# StuderA80ReproExtend_V0_2_RCA.net
KiCad netlist of a schematic drawn in Altium Designer
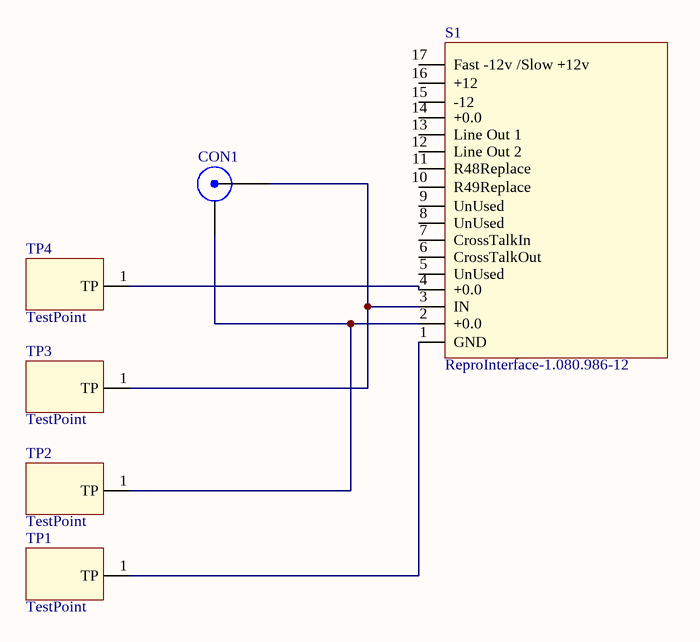
[diagram p0: StuderA80ReproExtend_V0.2_RCA.SchDoc]

(export (version "E")
  (design (tool "Eeschema 10.0.6"))
  (components
    (comp (ref "CON1")
      (value "RCA")
      (footprint "RCA-RJ255")
      (description "RCA Connector")
      (fields (field (name "PUBLISHER") "Altium Limited"))
      (libsource (lib "Connectors") (part "RCA"))
    )
    (comp (ref "S1")
      (value "ReproInterface-1.080.986-12")
      (footprint "ReproInterface")
      (description "Studer A80 RC Reproduce Card 1.080.986-12 Interface")
      (libsource (lib "Studer") (part "ReproInterface-1.080.986-12"))
    )
    (comp (ref "TP1")
      (value "TestPoint")
      (footprint "TP-1.0mm")
      (libsource (lib "Studer") (part "TestPoint"))
    )
    (comp (ref "TP2")
      (value "TestPoint")
      (footprint "TP-1.0mm")
      (libsource (lib "Studer") (part "TestPoint"))
    )
    (comp (ref "TP3")
      (value "TestPoint")
      (footprint "TP-1.0mm")
      (libsource (lib "Studer") (part "TestPoint"))
    )
    (comp (ref "TP4")
      (value "TestPoint")
      (footprint "TP-1.0mm")
      (libsource (lib "Studer") (part "TestPoint"))
    )
  )
  (nets
    (net (code "1") (name "Net-(CON1-X)") (class "Default")
      (node (ref "CON1") (pin "1") (pinfunction "X_1") (pintype "passive"))
      (node (ref "S1") (pin "3") (pinfunction "IN_3") (pintype "passive"))
      (node (ref "TP3") (pin "1") (pinfunction "TP_1") (pintype "passive"))
    )
    (net (code "2") (name "Net-(CON1-Y)") (class "Default")
      (node (ref "CON1") (pin "2") (pinfunction "Y_2") (pintype "passive"))
      (node (ref "S1") (pin "2") (pinfunction "+0.0_2") (pintype "passive"))
      (node (ref "TP2") (pin "1") (pinfunction "TP_1") (pintype "passive"))
    )
    (net (code "3") (name "Net-(S1-GND)") (class "Default")
      (node (ref "S1") (pin "1") (pinfunction "GND_1") (pintype "passive"))
      (node (ref "TP1") (pin "1") (pinfunction "TP_1") (pintype "passive"))
    )
    (net (code "4") (name "Net-(TP4-TP)") (class "Default")
      (node (ref "S1") (pin "4") (pinfunction "+0.0_4") (pintype "passive"))
      (node (ref "TP4") (pin "1") (pinfunction "TP_1") (pintype "passive"))
    )
    (net (code "5") (name "unconnected-(S1-+0.0-Pad14)") (class "Default")
      (node (ref "S1") (pin "14") (pinfunction "+0.0_14") (pintype "passive"))
    )
    (net (code "6") (name "unconnected-(S1-+12-Pad16)") (class "Default")
      (node (ref "S1") (pin "16") (pinfunction "+12_16") (pintype "passive"))
    )
    (net (code "7") (name "unconnected-(S1--12-Pad15)") (class "Default")
      (node (ref "S1") (pin "15") (pinfunction "-12_15") (pintype "passive"))
    )
    (net (code "8") (name "unconnected-(S1-CrossTalkIn-Pad7)") (class "Default")
      (node (ref "S1") (pin "7") (pinfunction "CrossTalkIn_7") (pintype "passive"))
    )
    (net (code "9") (name "unconnected-(S1-CrossTalkOut-Pad6)") (class "Default")
      (node (ref "S1") (pin "6") (pinfunction "CrossTalkOut_6") (pintype "passive"))
    )
    (net (code "10") (name "unconnected-(S1-Fast_-12v_{slash}Slow_+12v-Pad17)") (class "Default")
      (node (ref "S1") (pin "17") (pinfunction "Fast_-12v_/Slow_+12v_17") (pintype "passive"))
    )
    (net (code "11") (name "unconnected-(S1-Line_Out_1-Pad13)") (class "Default")
      (node (ref "S1") (pin "13") (pinfunction "Line_Out_1_13") (pintype "passive"))
    )
    (net (code "12") (name "unconnected-(S1-Line_Out_2-Pad12)") (class "Default")
      (node (ref "S1") (pin "12") (pinfunction "Line_Out_2_12") (pintype "passive"))
    )
    (net (code "13") (name "unconnected-(S1-R48Replace-Pad11)") (class "Default")
      (node (ref "S1") (pin "11") (pinfunction "R48Replace_11") (pintype "passive"))
    )
    (net (code "14") (name "unconnected-(S1-R49Replace-Pad10)") (class "Default")
      (node (ref "S1") (pin "10") (pinfunction "R49Replace_10") (pintype "passive"))
    )
    (net (code "15") (name "unconnected-(S1-UnUsed-Pad5)") (class "Default")
      (node (ref "S1") (pin "5") (pinfunction "UnUsed_5") (pintype "passive"))
    )
    (net (code "16") (name "unconnected-(S1-UnUsed-Pad8)") (class "Default")
      (node (ref "S1") (pin "8") (pinfunction "UnUsed_8") (pintype "passive"))
    )
    (net (code "17") (name "unconnected-(S1-UnUsed-Pad9)") (class "Default")
      (node (ref "S1") (pin "9") (pinfunction "UnUsed_9") (pintype "passive"))
    )
  )
)
